# sensor_v4.net
KiCad netlist of a schematic drawn in EAGLE
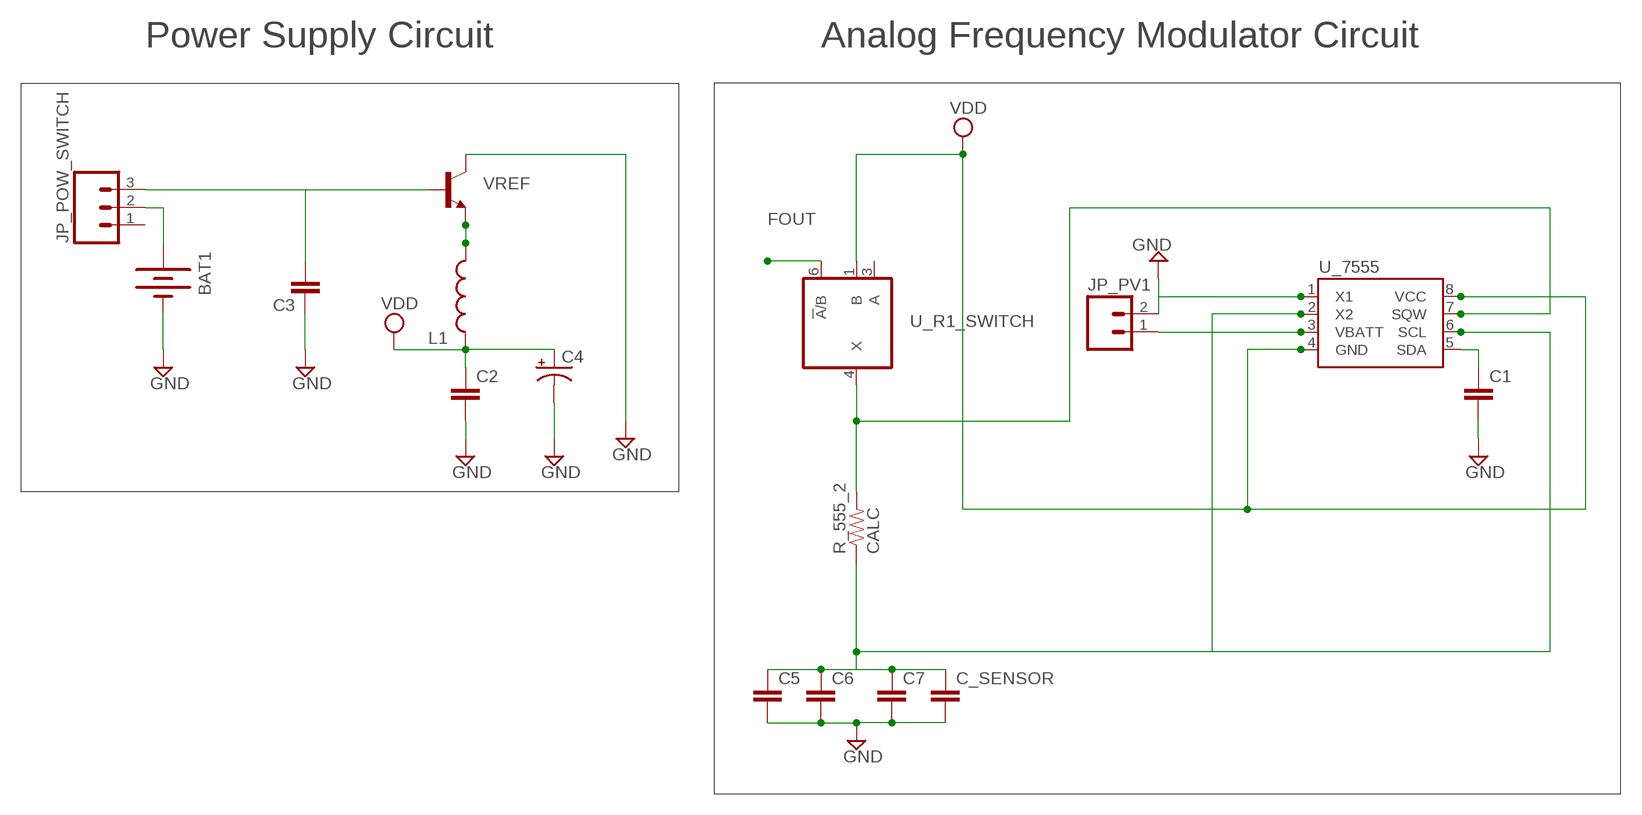
[diagram p0: schematic, sheet 1]

(export (version "E")
  (design (tool "Eeschema 10.0.6"))
  (components
    (comp (ref "BAT1")
      (value "BATTERY20PTH_LAB")
      (footprint "eagle-import:BATTCOM_20MM_PTH")
      (libsource (lib "eagle-import") (part "BATTERY20PTH_LAB"))
    )
    (comp (ref "C1")
      (value "CAP0603-CAP")
      (footprint "eagle-import:0603-CAP")
      (libsource (lib "eagle-import") (part "SparkFun-Capacitors_CAP0603-CAP"))
    )
    (comp (ref "C2")
      (value "CAP0603-CAP")
      (footprint "eagle-import:0603-CAP")
      (libsource (lib "eagle-import") (part "SparkFun-Capacitors_CAP0603-CAP"))
    )
    (comp (ref "C3")
      (value "CAP0603-CAP")
      (footprint "eagle-import:0603-CAP")
      (libsource (lib "eagle-import") (part "SparkFun-Capacitors_CAP0603-CAP"))
    )
    (comp (ref "C4")
      (value "CAP_POL1206")
      (footprint "eagle-import:EIA3216")
      (libsource (lib "eagle-import") (part "CAP_POL1206"))
    )
    (comp (ref "C5")
      (value "CAP0805")
      (footprint "eagle-import:0805")
      (libsource (lib "eagle-import") (part "CAP0805"))
    )
    (comp (ref "C6")
      (value "CAP0805")
      (footprint "eagle-import:0805")
      (libsource (lib "eagle-import") (part "CAP0805"))
    )
    (comp (ref "C7")
      (value "CAP0805")
      (footprint "eagle-import:0805")
      (libsource (lib "eagle-import") (part "CAP0805"))
    )
    (comp (ref "C_SENSOR")
      (value "CAP0805")
      (footprint "eagle-import:0805")
      (libsource (lib "eagle-import") (part "CAP0805"))
    )
    (comp (ref "JP_POW_SWITCH")
      (value "M03LOCK")
      (footprint "eagle-import:1X03_LOCK")
      (libsource (lib "eagle-import") (part "M03LOCK"))
    )
    (comp (ref "JP_PV1")
      (value "M02LOCK")
      (footprint "eagle-import:1X02_LOCK")
      (libsource (lib "eagle-import") (part "M02LOCK"))
    )
    (comp (ref "L1")
      (value "INDUCTOR0603")
      (footprint "eagle-import:0603")
      (libsource (lib "eagle-import") (part "INDUCTOR0603"))
    )
    (comp (ref "R_555_2")
      (value "CALC")
      (footprint "eagle-import:0805")
      (libsource (lib "eagle-import") (part "RESISTOR0805-RES"))
    )
    (comp (ref "U_7555")
      (value "DS1307SO8")
      (footprint "eagle-import:SO08")
      (libsource (lib "eagle-import") (part "DS1307SO8"))
    )
    (comp (ref "U_R1_SWITCH")
      (value "741G3157DCKR")
      (footprint "eagle-import:DCK_R-PDSO-G6")
      (libsource (lib "eagle-import") (part "741G3157DCKR"))
    )
    (comp (ref "U_VREF")
      (value "TRANSISTOR_NPNSOT23-3")
      (footprint "eagle-import:SOT23-3")
      (libsource (lib "eagle-import") (part "TRANSISTOR_NPNSOT23-3"))
    )
  )
  (nets
    (net (code "1") (name "/FOUT") (class "Default")
      (node (ref "JP_PV1") (pin "1") (pinfunction "1_1") (pintype "passive"))
      (node (ref "U_7555") (pin "3") (pinfunction "VBATT_3") (pintype "bidirectional"))
      (node (ref "U_R1_SWITCH") (pin "6") (pinfunction "~{A}/B_6") (pintype "input"))
    )
    (net (code "2") (name "/P2") (class "Default")
      (node (ref "C5") (pin "1") (pinfunction "1_1") (pintype "passive"))
      (node (ref "C6") (pin "1") (pinfunction "1_1") (pintype "passive"))
      (node (ref "C7") (pin "1") (pinfunction "1_1") (pintype "passive"))
      (node (ref "C_SENSOR") (pin "1") (pinfunction "1_1") (pintype "passive"))
      (node (ref "R_555_2") (pin "1") (pinfunction "1_1") (pintype "passive"))
      (node (ref "U_7555") (pin "2") (pinfunction "X2_2") (pintype "bidirectional"))
      (node (ref "U_7555") (pin "6") (pinfunction "SCL_6") (pintype "bidirectional"))
    )
    (net (code "3") (name "GND") (class "Default")
      (node (ref "BAT1") (pin "2") (pinfunction "-_2") (pintype "power_in"))
      (node (ref "C1") (pin "2") (pinfunction "2_2") (pintype "passive"))
      (node (ref "C2") (pin "2") (pinfunction "2_2") (pintype "passive"))
      (node (ref "C3") (pin "1") (pinfunction "1_1") (pintype "passive"))
      (node (ref "C4") (pin "C") (pinfunction "-_C") (pintype "passive"))
      (node (ref "C5") (pin "2") (pinfunction "2_2") (pintype "passive"))
      (node (ref "C6") (pin "2") (pinfunction "2_2") (pintype "passive"))
      (node (ref "C7") (pin "2") (pinfunction "2_2") (pintype "passive"))
      (node (ref "C_SENSOR") (pin "2") (pinfunction "2_2") (pintype "passive"))
      (node (ref "JP_PV1") (pin "2") (pinfunction "2_2") (pintype "passive"))
      (node (ref "U_7555") (pin "1") (pinfunction "X1_1") (pintype "bidirectional"))
      (node (ref "U_VREF") (pin "3") (pinfunction "C_3") (pintype "passive"))
    )
    (net (code "4") (name "Net-(BAT1-+)") (class "Default")
      (node (ref "BAT1") (pin "1") (pinfunction "+_1") (pintype "power_in"))
      (node (ref "JP_POW_SWITCH") (pin "2") (pinfunction "2_2") (pintype "passive"))
    )
    (net (code "5") (name "Net-(U_7555-SDA)") (class "Default")
      (node (ref "C1") (pin "1") (pinfunction "1_1") (pintype "passive"))
      (node (ref "U_7555") (pin "5") (pinfunction "SDA_5") (pintype "bidirectional"))
    )
    (net (code "6") (name "Net-(U_7555-SQW)") (class "Default")
      (node (ref "R_555_2") (pin "2") (pinfunction "2_2") (pintype "passive"))
      (node (ref "U_7555") (pin "7") (pinfunction "SQW_7") (pintype "bidirectional"))
      (node (ref "U_R1_SWITCH") (pin "4") (pinfunction "X_4") (pintype "bidirectional"))
    )
    (net (code "7") (name "Net-(U_VREF-B)") (class "Default")
      (node (ref "C3") (pin "2") (pinfunction "2_2") (pintype "passive"))
      (node (ref "JP_POW_SWITCH") (pin "3") (pinfunction "3_3") (pintype "passive"))
      (node (ref "U_VREF") (pin "1") (pinfunction "B_1") (pintype "passive"))
    )
    (net (code "8") (name "Net-(U_VREF-E)") (class "Default")
      (node (ref "L1") (pin "2") (pinfunction "2_2") (pintype "passive"))
      (node (ref "U_VREF") (pin "2") (pinfunction "E_2") (pintype "passive"))
    )
    (net (code "9") (name "VDD") (class "Default")
      (node (ref "C2") (pin "1") (pinfunction "1_1") (pintype "passive"))
      (node (ref "C4") (pin "A") (pinfunction "+_A") (pintype "passive"))
      (node (ref "L1") (pin "1") (pinfunction "1_1") (pintype "passive"))
      (node (ref "U_7555") (pin "4") (pinfunction "GND_4") (pintype "bidirectional"))
      (node (ref "U_7555") (pin "8") (pinfunction "VCC_8") (pintype "bidirectional"))
      (node (ref "U_R1_SWITCH") (pin "1") (pinfunction "B_1") (pintype "bidirectional"))
    )
    (net (code "10") (name "unconnected-(JP_POW_SWITCH-Pad1)") (class "Default")
      (node (ref "JP_POW_SWITCH") (pin "1") (pinfunction "1_1") (pintype "passive"))
    )
    (net (code "11") (name "unconnected-(U_R1_SWITCHA-A-Pad3)") (class "Default")
      (node (ref "U_R1_SWITCH") (pin "3") (pinfunction "A_3") (pintype "bidirectional"))
    )
  )
)
